# Buzzer.net
KiCad netlist of a schematic drawn in Altium Designer
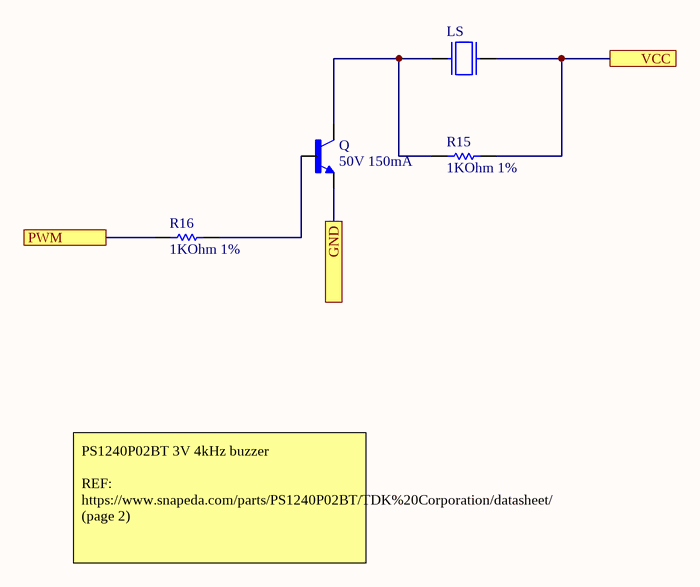
[diagram p0: Buzzer.SchDoc]

(export (version "E")
  (design (tool "Eeschema 10.0.6"))
  (components
    (comp (ref "LS")
      (value "PS1240P02BT")
      (footprint "PS1240P02BT")
      (description "TDK - PS1240P02BT - BUZZER, PIEZO, 70DB, 12.2MM")
      (fields (field (name "MF") "TDK"))
      (libsource (lib "Schematics") (part "PS1240P02BT"))
    )
    (comp (ref "Q")
      (value "50V 150mA")
      (footprint "2SC1815")
      (description "Transistor GP BJT NPN 50V 150mA 3-Pin TO-92 Box 2SC1815")
      (fields (field (name "MP") "2SC1815") (field (name "MF") "Central Semiconductor"))
      (libsource (lib "CommonComponents_DIY") (part "2SC1815"))
    )
    (comp (ref "R15")
      (value "1KOhm 1%")
      (footprint "RESC0603(1608)_M")
      (description "1K 0.1W 1% 0603 (1608 Metric)  SMD")
      (fields (field (name "TOLERANCE") "1 %") (field (name "POWER") "0.1 W"))
      (libsource (lib "Altium Content Vault") (part "RES"))
    )
    (comp (ref "R16")
      (value "1KOhm 1%")
      (footprint "RESC0603(1608)_M")
      (description "1K 0.1W 1% 0603 (1608 Metric)  SMD")
      (fields (field (name "TOLERANCE") "1 %") (field (name "POWER") "0.1 W"))
      (libsource (lib "Altium Content Vault") (part "RES"))
    )
  )
  (nets
    (net (code "1") (name "/GND") (class "Default")
      (node (ref "Q") (pin "1") (pinfunction "E_1") (pintype "passive"))
    )
    (net (code "2") (name "/PWM") (class "Default")
      (node (ref "R16") (pin "1") (pinfunction "1_1") (pintype "passive"))
    )
    (net (code "3") (name "/VCC") (class "Default")
      (node (ref "LS") (pin "2") (pinfunction "2_2") (pintype "passive"))
      (node (ref "R15") (pin "2") (pinfunction "2_2") (pintype "passive"))
    )
    (net (code "4") (name "Net-(Q-B)") (class "Default")
      (node (ref "Q") (pin "3") (pinfunction "B_3") (pintype "passive"))
      (node (ref "R16") (pin "2") (pinfunction "2_2") (pintype "passive"))
    )
    (net (code "5") (name "Net-(Q-C)") (class "Default")
      (node (ref "LS") (pin "1") (pinfunction "1_1") (pintype "passive"))
      (node (ref "Q") (pin "2") (pinfunction "C_2") (pintype "passive"))
      (node (ref "R15") (pin "1") (pinfunction "1_1") (pintype "passive"))
    )
  )
)
